# lab3-2.net
KiCad netlist of a schematic drawn in EAGLE
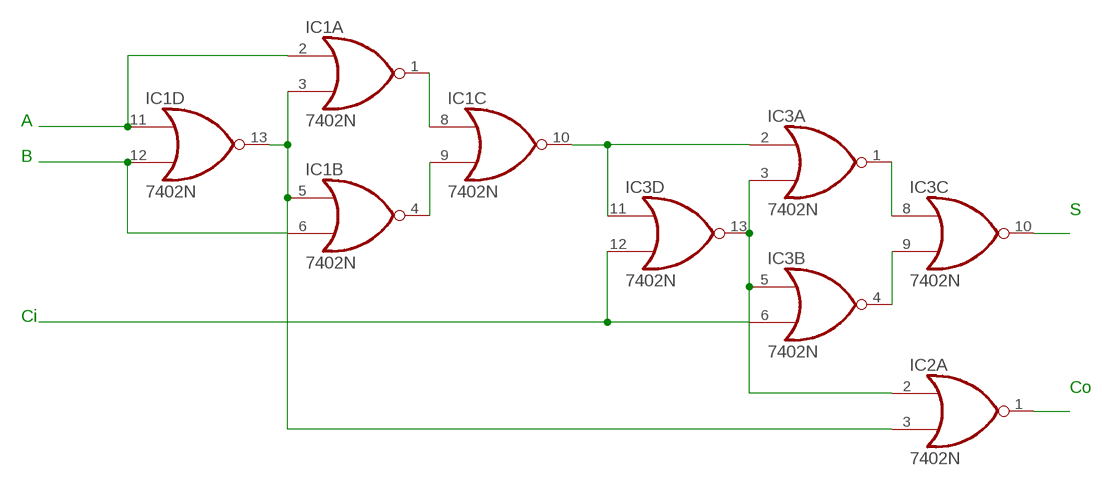
[diagram p0: schematic, sheet 1]

(export (version "E")
  (design (tool "Eeschema 10.0.6"))
  (components
    (comp (ref "IC1")
      (value "7402N")
      (footprint "eagle-import:DIL14")
      (libsource (lib "eagle-import") (part "7402N"))
    )
    (comp (ref "IC2")
      (value "7402N")
      (footprint "eagle-import:DIL14")
      (libsource (lib "eagle-import") (part "7402N"))
    )
    (comp (ref "IC3")
      (value "7402N")
      (footprint "eagle-import:DIL14")
      (libsource (lib "eagle-import") (part "7402N"))
    )
  )
  (nets
    (net (code "1") (name "Net-(IC1A-I0)") (class "Default")
      (node (ref "IC1") (pin "11") (pinfunction "I0_11") (pintype "input"))
      (node (ref "IC1") (pin "2") (pinfunction "I0_2") (pintype "input"))
    )
    (net (code "2") (name "Net-(IC1A-I1)") (class "Default")
      (node (ref "IC1") (pin "13") (pinfunction "O_13") (pintype "output"))
      (node (ref "IC1") (pin "3") (pinfunction "I1_3") (pintype "input"))
      (node (ref "IC1") (pin "5") (pinfunction "I0_5") (pintype "input"))
      (node (ref "IC2") (pin "3") (pinfunction "I1_3") (pintype "input"))
    )
    (net (code "3") (name "Net-(IC1A-O)") (class "Default")
      (node (ref "IC1") (pin "1") (pinfunction "O_1") (pintype "output"))
      (node (ref "IC1") (pin "8") (pinfunction "I0_8") (pintype "input"))
    )
    (net (code "4") (name "Net-(IC1B-I1)") (class "Default")
      (node (ref "IC1") (pin "12") (pinfunction "I1_12") (pintype "input"))
      (node (ref "IC1") (pin "6") (pinfunction "I1_6") (pintype "input"))
    )
    (net (code "5") (name "Net-(IC1B-O)") (class "Default")
      (node (ref "IC1") (pin "4") (pinfunction "O_4") (pintype "output"))
      (node (ref "IC1") (pin "9") (pinfunction "I1_9") (pintype "input"))
    )
    (net (code "6") (name "Net-(IC1C-O)") (class "Default")
      (node (ref "IC1") (pin "10") (pinfunction "O_10") (pintype "output"))
      (node (ref "IC3") (pin "11") (pinfunction "I0_11") (pintype "input"))
      (node (ref "IC3") (pin "2") (pinfunction "I0_2") (pintype "input"))
    )
    (net (code "7") (name "Net-(IC2A-I0)") (class "Default")
      (node (ref "IC2") (pin "2") (pinfunction "I0_2") (pintype "input"))
      (node (ref "IC3") (pin "13") (pinfunction "O_13") (pintype "output"))
      (node (ref "IC3") (pin "3") (pinfunction "I1_3") (pintype "input"))
      (node (ref "IC3") (pin "5") (pinfunction "I0_5") (pintype "input"))
    )
    (net (code "8") (name "Net-(IC3A-O)") (class "Default")
      (node (ref "IC3") (pin "1") (pinfunction "O_1") (pintype "output"))
      (node (ref "IC3") (pin "8") (pinfunction "I0_8") (pintype "input"))
    )
    (net (code "9") (name "Net-(IC3B-I1)") (class "Default")
      (node (ref "IC3") (pin "12") (pinfunction "I1_12") (pintype "input"))
      (node (ref "IC3") (pin "6") (pinfunction "I1_6") (pintype "input"))
    )
    (net (code "10") (name "Net-(IC3B-O)") (class "Default")
      (node (ref "IC3") (pin "4") (pinfunction "O_4") (pintype "output"))
      (node (ref "IC3") (pin "9") (pinfunction "I1_9") (pintype "input"))
    )
    (net (code "11") (name "unconnected-(IC2A-O-Pad1)") (class "Default")
      (node (ref "IC2") (pin "1") (pinfunction "O_1") (pintype "output"))
    )
    (net (code "12") (name "unconnected-(IC3C-O-Pad10)") (class "Default")
      (node (ref "IC3") (pin "10") (pinfunction "O_10") (pintype "output"))
    )
  )
)
